# M2male_miniDP.net
KiCad netlist of a schematic drawn in Altium Designer
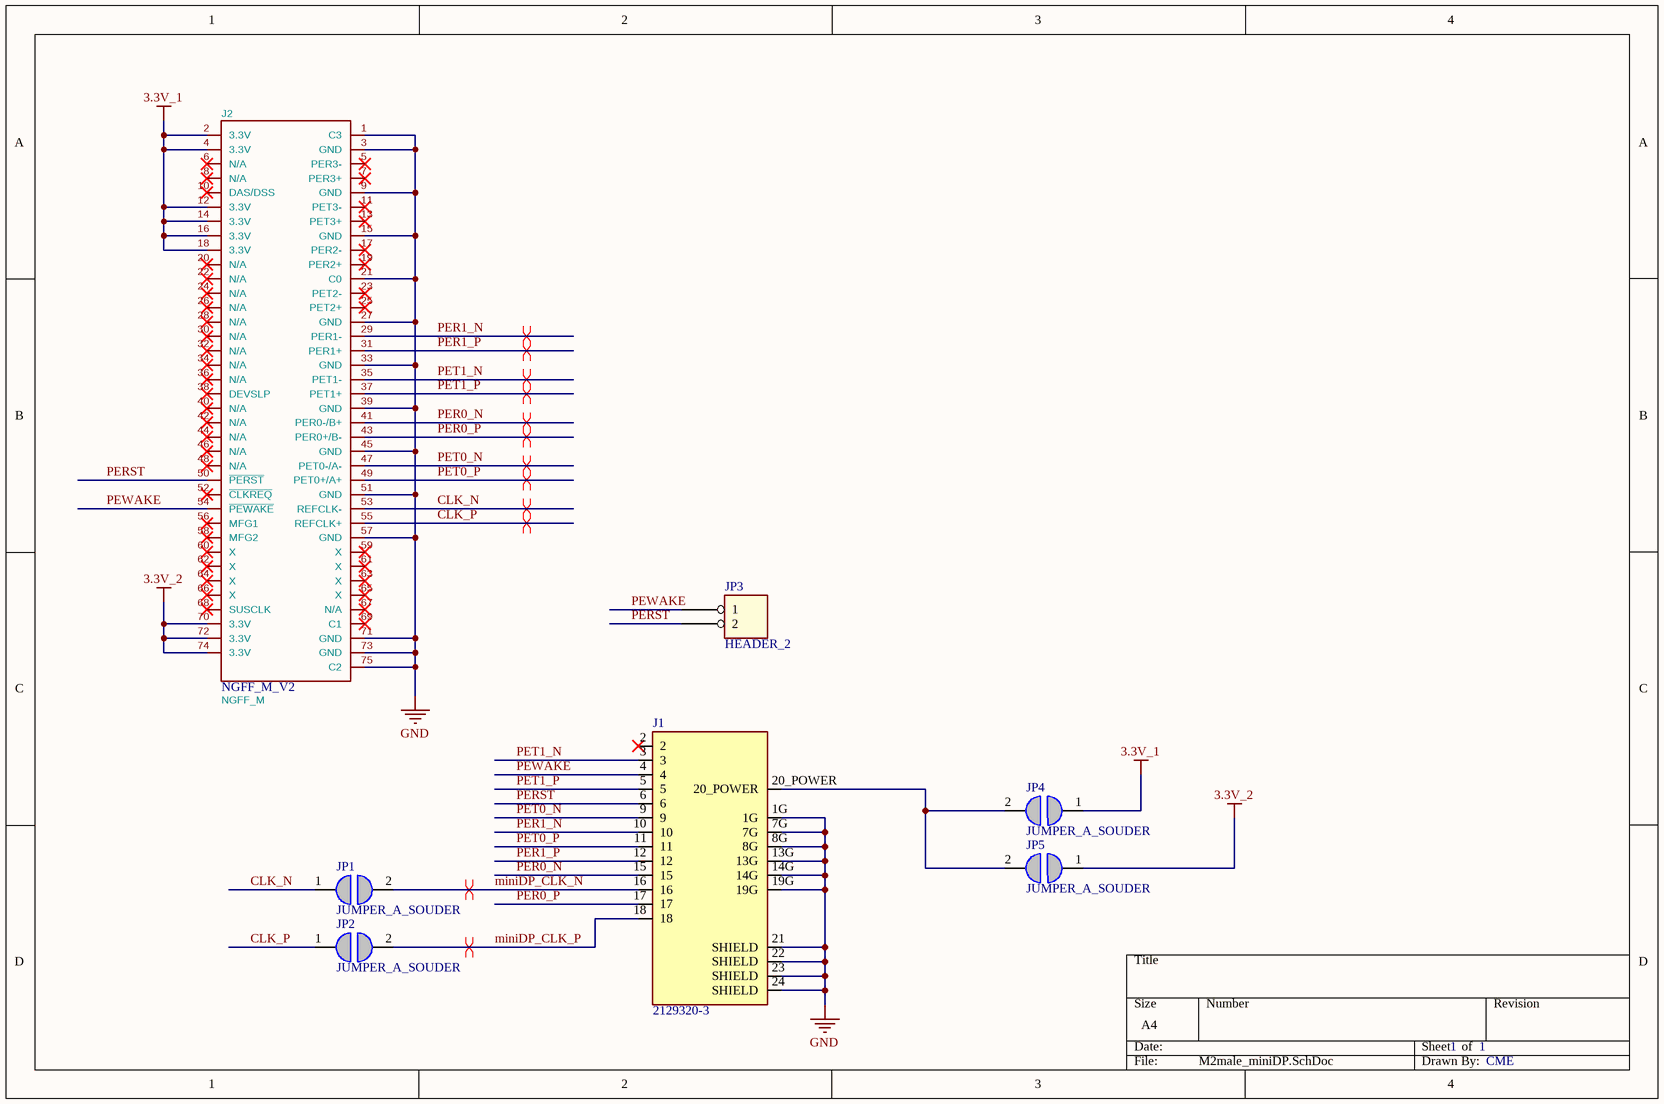
[diagram p0: M2male_miniDP.SchDoc]

(export (version "E")
  (design (tool "Eeschema 10.0.6"))
  (components
    (comp (ref "J1")
      (value "2129320-3")
      (footprint "CME_LIB:CONN_2129320-3")
      (description "Conn Display Port RCP 20 POS 0.9mm/1.8mm Solder RA Thru-Hole 20 Terminal 1 Port T/R")
      (fields (field (name "DIGI-KEY_PART_NUMBER") "A120537CT-ND") (field (name "MF") "TE Connectivity"))
      (libsource (lib "CME_LIB") (part "2129320-3"))
    )
    (comp (ref "J2")
      (value "NGFF_M_V2")
      (footprint "M2male_M2female_miniDP:M.2-M-KEY-2280-V2")
      (fields (field (name "ALTIUM_VALUE") "NGFF_M"))
      (libsource (lib "M2male_M2female_miniDP") (part "NGFF_M_V2"))
    )
    (comp (ref "JP1")
      (value "JUMPER_A_SOUDER")
      (footprint "JUMPER_A_SOUDER (0201)")
      (description "Pont à souder sur print")
      (libsource (lib "") (part "JUMPER_A_SOUDER_1"))
    )
    (comp (ref "JP2")
      (value "JUMPER_A_SOUDER")
      (footprint "JUMPER_A_SOUDER (0201)")
      (description "Pont à souder sur print")
      (libsource (lib "") (part "JUMPER_A_SOUDER_1"))
    )
    (comp (ref "JP3")
      (value "HEADER_2")
      (footprint "Barette simple 2.54mm  2 POLES 90 degres MALE")
      (description "Barrette mâle 90 degrés 2P 2,54 mm")
      (fields (field (name "MANUFACTURER") "TE Connectivity"))
      (libsource (lib "DatabaseReDS") (part "HEADER_2"))
    )
    (comp (ref "JP4")
      (value "JUMPER_A_SOUDER")
      (footprint "JUMPER_A_SOUDER (0201)")
      (description "Pont à souder sur print")
      (libsource (lib "DatabaseReDS") (part "JUMPER_A_SOUDER"))
    )
    (comp (ref "JP5")
      (value "JUMPER_A_SOUDER")
      (footprint "JUMPER_A_SOUDER (0201)")
      (description "Pont à souder sur print")
      (libsource (lib "DatabaseReDS") (part "JUMPER_A_SOUDER"))
    )
  )
  (nets
    (net (code "1") (name "/CLK_N") (class "Default")
      (node (ref "J2") (pin "53") (pinfunction "REFCLK-_53") (pintype "passive"))
      (node (ref "JP1") (pin "1") (pinfunction "1_1") (pintype "passive"))
    )
    (net (code "2") (name "/CLK_P") (class "Default")
      (node (ref "J2") (pin "55") (pinfunction "REFCLK+_55") (pintype "passive"))
      (node (ref "JP2") (pin "1") (pinfunction "1_1") (pintype "passive"))
    )
    (net (code "3") (name "/PER0_N") (class "Default")
      (node (ref "J1") (pin "15") (pinfunction "15_15") (pintype "passive"))
      (node (ref "J2") (pin "41") (pinfunction "PER0-/B+_41") (pintype "passive"))
    )
    (net (code "4") (name "/PER0_P") (class "Default")
      (node (ref "J1") (pin "17") (pinfunction "17_17") (pintype "passive"))
      (node (ref "J2") (pin "43") (pinfunction "PER0+/B-_43") (pintype "passive"))
    )
    (net (code "5") (name "/PER1_N") (class "Default")
      (node (ref "J1") (pin "10") (pinfunction "10_10") (pintype "passive"))
      (node (ref "J2") (pin "29") (pinfunction "PER1-_29") (pintype "passive"))
    )
    (net (code "6") (name "/PER1_P") (class "Default")
      (node (ref "J1") (pin "12") (pinfunction "12_12") (pintype "passive"))
      (node (ref "J2") (pin "31") (pinfunction "PER1+_31") (pintype "passive"))
    )
    (net (code "7") (name "/PERST") (class "Default")
      (node (ref "J1") (pin "6") (pinfunction "6_6") (pintype "passive"))
      (node (ref "J2") (pin "50") (pinfunction "~{PERST}_50") (pintype "passive"))
      (node (ref "JP3") (pin "2") (pinfunction "2_2") (pintype "passive"))
    )
    (net (code "8") (name "/PET0_N") (class "Default")
      (node (ref "J1") (pin "9") (pinfunction "9_9") (pintype "passive"))
      (node (ref "J2") (pin "47") (pinfunction "PET0-/A-_47") (pintype "passive"))
    )
    (net (code "9") (name "/PET0_P") (class "Default")
      (node (ref "J1") (pin "11") (pinfunction "11_11") (pintype "passive"))
      (node (ref "J2") (pin "49") (pinfunction "PET0+/A+_49") (pintype "passive"))
    )
    (net (code "10") (name "/PET1_N") (class "Default")
      (node (ref "J1") (pin "3") (pinfunction "3_3") (pintype "passive"))
      (node (ref "J2") (pin "35") (pinfunction "PET1-_35") (pintype "passive"))
    )
    (net (code "11") (name "/PET1_P") (class "Default")
      (node (ref "J1") (pin "5") (pinfunction "5_5") (pintype "passive"))
      (node (ref "J2") (pin "37") (pinfunction "PET1+_37") (pintype "passive"))
    )
    (net (code "12") (name "/PEWAKE") (class "Default")
      (node (ref "J1") (pin "4") (pinfunction "4_4") (pintype "passive"))
      (node (ref "J2") (pin "54") (pinfunction "~{PEWAKE}_54") (pintype "passive"))
      (node (ref "JP3") (pin "1") (pinfunction "1_1") (pintype "passive"))
    )
    (net (code "13") (name "/miniDP_CLK_N") (class "Default")
      (node (ref "J1") (pin "16") (pinfunction "16_16") (pintype "passive"))
      (node (ref "JP1") (pin "2") (pinfunction "2_2") (pintype "passive"))
    )
    (net (code "14") (name "/miniDP_CLK_P") (class "Default")
      (node (ref "J1") (pin "18") (pinfunction "18_18") (pintype "passive"))
      (node (ref "JP2") (pin "2") (pinfunction "2_2") (pintype "passive"))
    )
    (net (code "15") (name "3.3V_1") (class "Default")
      (node (ref "J2") (pin "12") (pinfunction "3.3V_12") (pintype "passive"))
      (node (ref "J2") (pin "14") (pinfunction "3.3V_14") (pintype "passive"))
      (node (ref "J2") (pin "16") (pinfunction "3.3V_16") (pintype "passive"))
      (node (ref "J2") (pin "18") (pinfunction "3.3V_18") (pintype "passive"))
      (node (ref "J2") (pin "2") (pinfunction "3.3V_2") (pintype "passive"))
      (node (ref "J2") (pin "4") (pinfunction "3.3V_4") (pintype "passive"))
      (node (ref "JP4") (pin "1") (pinfunction "1_1") (pintype "passive"))
    )
    (net (code "16") (name "3.3V_2") (class "Default")
      (node (ref "J2") (pin "70") (pinfunction "3.3V_70") (pintype "passive"))
      (node (ref "J2") (pin "72") (pinfunction "3.3V_72") (pintype "passive"))
      (node (ref "J2") (pin "74") (pinfunction "3.3V_74") (pintype "passive"))
      (node (ref "JP5") (pin "1") (pinfunction "1_1") (pintype "passive"))
    )
    (net (code "17") (name "GND") (class "Default")
      (node (ref "J1") (pin "13G") (pinfunction "13G_13G") (pintype "passive"))
      (node (ref "J1") (pin "14G") (pinfunction "14G_14G") (pintype "passive"))
      (node (ref "J1") (pin "19G") (pinfunction "19G_19G") (pintype "passive"))
      (node (ref "J1") (pin "1G") (pinfunction "1G_1G") (pintype "passive"))
      (node (ref "J1") (pin "21") (pinfunction "SHIELD_21") (pintype "passive"))
      (node (ref "J1") (pin "22") (pinfunction "SHIELD_22") (pintype "passive"))
      (node (ref "J1") (pin "23") (pinfunction "SHIELD_23") (pintype "passive"))
      (node (ref "J1") (pin "24") (pinfunction "SHIELD_24") (pintype "passive"))
      (node (ref "J1") (pin "7G") (pinfunction "7G_7G") (pintype "passive"))
      (node (ref "J1") (pin "8G") (pinfunction "8G_8G") (pintype "passive"))
      (node (ref "J2") (pin "1") (pinfunction "C3_1") (pintype "passive"))
      (node (ref "J2") (pin "15") (pinfunction "GND_15") (pintype "passive"))
      (node (ref "J2") (pin "21") (pinfunction "C0_21") (pintype "passive"))
      (node (ref "J2") (pin "27") (pinfunction "GND_27") (pintype "passive"))
      (node (ref "J2") (pin "3") (pinfunction "GND_3") (pintype "passive"))
      (node (ref "J2") (pin "33") (pinfunction "GND_33") (pintype "passive"))
      (node (ref "J2") (pin "39") (pinfunction "GND_39") (pintype "passive"))
      (node (ref "J2") (pin "45") (pinfunction "GND_45") (pintype "passive"))
      (node (ref "J2") (pin "51") (pinfunction "GND_51") (pintype "passive"))
      (node (ref "J2") (pin "57") (pinfunction "GND_57") (pintype "passive"))
      (node (ref "J2") (pin "71") (pinfunction "GND_71") (pintype "passive"))
      (node (ref "J2") (pin "73") (pinfunction "GND_73") (pintype "passive"))
      (node (ref "J2") (pin "75") (pinfunction "C2_75") (pintype "passive"))
      (node (ref "J2") (pin "9") (pinfunction "GND_9") (pintype "passive"))
    )
    (net (code "18") (name "Net-(J1-Pad20_POWER)") (class "Default")
      (node (ref "J1") (pin "20_POWER") (pinfunction "20_POWER_20_POWER") (pintype "passive"))
      (node (ref "JP4") (pin "2") (pinfunction "2_2") (pintype "passive"))
      (node (ref "JP5") (pin "2") (pinfunction "2_2") (pintype "passive"))
    )
    (net (code "19") (name "unconnected-(J1-Pad2)") (class "Default")
      (node (ref "J1") (pin "2") (pinfunction "2_2") (pintype "passive+no_connect"))
    )
    (net (code "20") (name "unconnected-(J2-C1-Pad69)") (class "Default")
      (node (ref "J2") (pin "69") (pinfunction "C1_69") (pintype "passive+no_connect"))
    )
    (net (code "21") (name "unconnected-(J2-DAS{slash}DSS-Pad10)") (class "Default")
      (node (ref "J2") (pin "10") (pinfunction "DAS/DSS_10") (pintype "passive+no_connect"))
    )
    (net (code "22") (name "unconnected-(J2-DEVSLP-Pad38)") (class "Default")
      (node (ref "J2") (pin "38") (pinfunction "DEVSLP_38") (pintype "passive+no_connect"))
    )
    (net (code "23") (name "unconnected-(J2-MFG1-Pad56)") (class "Default")
      (node (ref "J2") (pin "56") (pinfunction "MFG1_56") (pintype "passive+no_connect"))
    )
    (net (code "24") (name "unconnected-(J2-MFG2-Pad58)") (class "Default")
      (node (ref "J2") (pin "58") (pinfunction "MFG2_58") (pintype "passive+no_connect"))
    )
    (net (code "25") (name "unconnected-(J2-N{slash}A-Pad6)") (class "Default")
      (node (ref "J2") (pin "6") (pinfunction "N/A_6") (pintype "passive+no_connect"))
    )
    (net (code "26") (name "unconnected-(J2-N{slash}A-Pad8)") (class "Default")
      (node (ref "J2") (pin "8") (pinfunction "N/A_8") (pintype "passive+no_connect"))
    )
    (net (code "27") (name "unconnected-(J2-N{slash}A-Pad20)") (class "Default")
      (node (ref "J2") (pin "20") (pinfunction "N/A_20") (pintype "passive+no_connect"))
    )
    (net (code "28") (name "unconnected-(J2-N{slash}A-Pad22)") (class "Default")
      (node (ref "J2") (pin "22") (pinfunction "N/A_22") (pintype "passive+no_connect"))
    )
    (net (code "29") (name "unconnected-(J2-N{slash}A-Pad24)") (class "Default")
      (node (ref "J2") (pin "24") (pinfunction "N/A_24") (pintype "passive+no_connect"))
    )
    (net (code "30") (name "unconnected-(J2-N{slash}A-Pad26)") (class "Default")
      (node (ref "J2") (pin "26") (pinfunction "N/A_26") (pintype "passive+no_connect"))
    )
    (net (code "31") (name "unconnected-(J2-N{slash}A-Pad28)") (class "Default")
      (node (ref "J2") (pin "28") (pinfunction "N/A_28") (pintype "passive+no_connect"))
    )
    (net (code "32") (name "unconnected-(J2-N{slash}A-Pad30)") (class "Default")
      (node (ref "J2") (pin "30") (pinfunction "N/A_30") (pintype "passive+no_connect"))
    )
    (net (code "33") (name "unconnected-(J2-N{slash}A-Pad32)") (class "Default")
      (node (ref "J2") (pin "32") (pinfunction "N/A_32") (pintype "passive+no_connect"))
    )
    (net (code "34") (name "unconnected-(J2-N{slash}A-Pad34)") (class "Default")
      (node (ref "J2") (pin "34") (pinfunction "N/A_34") (pintype "passive+no_connect"))
    )
    (net (code "35") (name "unconnected-(J2-N{slash}A-Pad36)") (class "Default")
      (node (ref "J2") (pin "36") (pinfunction "N/A_36") (pintype "passive+no_connect"))
    )
    (net (code "36") (name "unconnected-(J2-N{slash}A-Pad40)") (class "Default")
      (node (ref "J2") (pin "40") (pinfunction "N/A_40") (pintype "passive+no_connect"))
    )
    (net (code "37") (name "unconnected-(J2-N{slash}A-Pad42)") (class "Default")
      (node (ref "J2") (pin "42") (pinfunction "N/A_42") (pintype "passive+no_connect"))
    )
    (net (code "38") (name "unconnected-(J2-N{slash}A-Pad44)") (class "Default")
      (node (ref "J2") (pin "44") (pinfunction "N/A_44") (pintype "passive+no_connect"))
    )
    (net (code "39") (name "unconnected-(J2-N{slash}A-Pad46)") (class "Default")
      (node (ref "J2") (pin "46") (pinfunction "N/A_46") (pintype "passive+no_connect"))
    )
    (net (code "40") (name "unconnected-(J2-N{slash}A-Pad48)") (class "Default")
      (node (ref "J2") (pin "48") (pinfunction "N/A_48") (pintype "passive+no_connect"))
    )
    (net (code "41") (name "unconnected-(J2-N{slash}A-Pad67)") (class "Default")
      (node (ref "J2") (pin "67") (pinfunction "N/A_67") (pintype "passive+no_connect"))
    )
    (net (code "42") (name "unconnected-(J2-PER2+-Pad19)") (class "Default")
      (node (ref "J2") (pin "19") (pinfunction "PER2+_19") (pintype "passive+no_connect"))
    )
    (net (code "43") (name "unconnected-(J2-PER2--Pad17)") (class "Default")
      (node (ref "J2") (pin "17") (pinfunction "PER2-_17") (pintype "passive+no_connect"))
    )
    (net (code "44") (name "unconnected-(J2-PER3+-Pad7)") (class "Default")
      (node (ref "J2") (pin "7") (pinfunction "PER3+_7") (pintype "passive+no_connect"))
    )
    (net (code "45") (name "unconnected-(J2-PER3--Pad5)") (class "Default")
      (node (ref "J2") (pin "5") (pinfunction "PER3-_5") (pintype "passive+no_connect"))
    )
    (net (code "46") (name "unconnected-(J2-PET2+-Pad25)") (class "Default")
      (node (ref "J2") (pin "25") (pinfunction "PET2+_25") (pintype "passive+no_connect"))
    )
    (net (code "47") (name "unconnected-(J2-PET2--Pad23)") (class "Default")
      (node (ref "J2") (pin "23") (pinfunction "PET2-_23") (pintype "passive+no_connect"))
    )
    (net (code "48") (name "unconnected-(J2-PET3+-Pad13)") (class "Default")
      (node (ref "J2") (pin "13") (pinfunction "PET3+_13") (pintype "passive+no_connect"))
    )
    (net (code "49") (name "unconnected-(J2-PET3--Pad11)") (class "Default")
      (node (ref "J2") (pin "11") (pinfunction "PET3-_11") (pintype "passive+no_connect"))
    )
    (net (code "50") (name "unconnected-(J2-SUSCLK-Pad68)") (class "Default")
      (node (ref "J2") (pin "68") (pinfunction "SUSCLK_68") (pintype "passive+no_connect"))
    )
    (net (code "51") (name "unconnected-(J2-X-Pad59)") (class "Default")
      (node (ref "J2") (pin "59") (pinfunction "X_59") (pintype "passive+no_connect"))
    )
    (net (code "52") (name "unconnected-(J2-X-Pad60)") (class "Default")
      (node (ref "J2") (pin "60") (pinfunction "X_60") (pintype "passive+no_connect"))
    )
    (net (code "53") (name "unconnected-(J2-X-Pad61)") (class "Default")
      (node (ref "J2") (pin "61") (pinfunction "X_61") (pintype "passive+no_connect"))
    )
    (net (code "54") (name "unconnected-(J2-X-Pad62)") (class "Default")
      (node (ref "J2") (pin "62") (pinfunction "X_62") (pintype "passive+no_connect"))
    )
    (net (code "55") (name "unconnected-(J2-X-Pad63)") (class "Default")
      (node (ref "J2") (pin "63") (pinfunction "X_63") (pintype "passive+no_connect"))
    )
    (net (code "56") (name "unconnected-(J2-X-Pad64)") (class "Default")
      (node (ref "J2") (pin "64") (pinfunction "X_64") (pintype "passive+no_connect"))
    )
    (net (code "57") (name "unconnected-(J2-X-Pad65)") (class "Default")
      (node (ref "J2") (pin "65") (pinfunction "X_65") (pintype "passive+no_connect"))
    )
    (net (code "58") (name "unconnected-(J2-X-Pad66)") (class "Default")
      (node (ref "J2") (pin "66") (pinfunction "X_66") (pintype "passive+no_connect"))
    )
    (net (code "59") (name "unconnected-(J2-~{CLKREQ}-Pad52)") (class "Default")
      (node (ref "J2") (pin "52") (pinfunction "~{CLKREQ}_52") (pintype "passive+no_connect"))
    )
  )
)
